# parallella_io.net
KiCad netlist of a schematic drawn in EAGLE
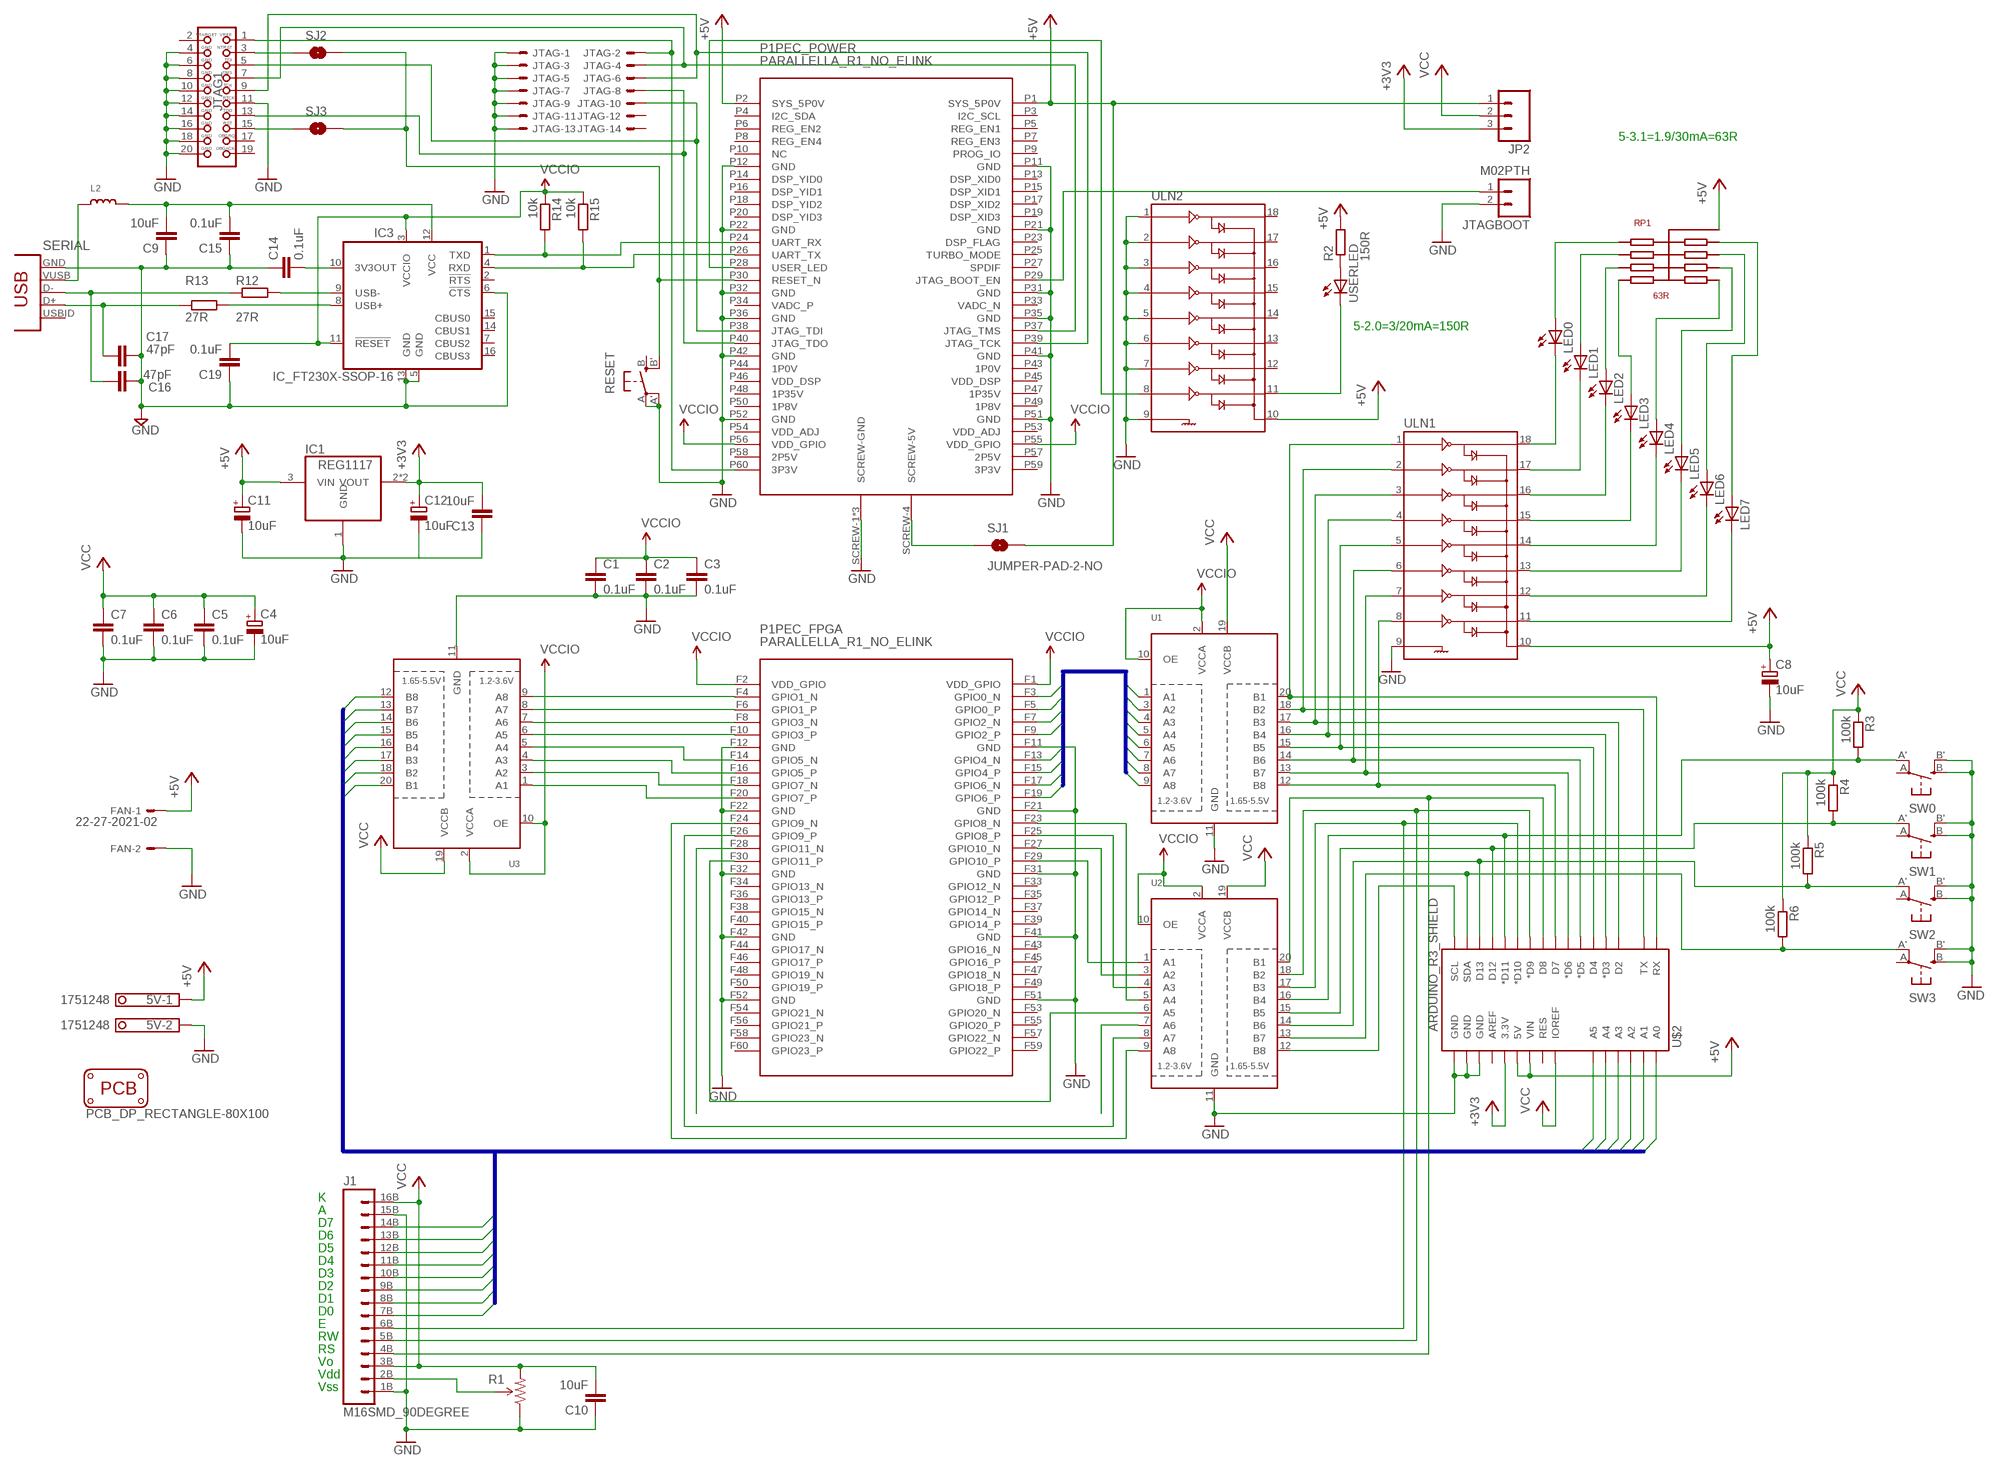
[diagram p0: schematic, sheet 1]

(export (version "E")
  (design (tool "Eeschema 10.0.6"))
  (components
    (comp (ref "5V")
      (value "1751248")
      (footprint "eagle-import:1751248")
      (libsource (lib "eagle-import") (part "1751248"))
    )
    (comp (ref "C1")
      (value "0.1uF")
      (footprint "eagle-import:C0603-N")
      (libsource (lib "eagle-import") (part "C-EUC0603-N"))
    )
    (comp (ref "C2")
      (value "0.1uF")
      (footprint "eagle-import:C0603-N")
      (libsource (lib "eagle-import") (part "C-EUC0603-N"))
    )
    (comp (ref "C3")
      (value "0.1uF")
      (footprint "eagle-import:C0603-N")
      (libsource (lib "eagle-import") (part "C-EUC0603-N"))
    )
    (comp (ref "C4")
      (value "10uF")
      (footprint "eagle-import:D_7343-31W")
      (libsource (lib "eagle-import") (part "CPOL-EUD/7343-31W"))
    )
    (comp (ref "C5")
      (value "0.1uF")
      (footprint "eagle-import:C0603-N")
      (libsource (lib "eagle-import") (part "C-EUC0603-N"))
    )
    (comp (ref "C6")
      (value "0.1uF")
      (footprint "eagle-import:C0603-N")
      (libsource (lib "eagle-import") (part "C-EUC0603-N"))
    )
    (comp (ref "C7")
      (value "0.1uF")
      (footprint "eagle-import:C0603-N")
      (libsource (lib "eagle-import") (part "C-EUC0603-N"))
    )
    (comp (ref "C8")
      (value "10uF")
      (footprint "eagle-import:D_7343-31W")
      (libsource (lib "eagle-import") (part "CPOL-EUD/7343-31W"))
    )
    (comp (ref "C9")
      (value "10uF")
      (footprint "eagle-import:C0603-N")
      (libsource (lib "eagle-import") (part "C-EUC0603-N"))
    )
    (comp (ref "C10")
      (value "10uF")
      (footprint "eagle-import:C0603-N")
      (libsource (lib "eagle-import") (part "C-EUC0603-N"))
    )
    (comp (ref "C11")
      (value "10uF")
      (footprint "eagle-import:D_7343-31W")
      (libsource (lib "eagle-import") (part "CPOL-EUD/7343-31W"))
    )
    (comp (ref "C12")
      (value "10uF")
      (footprint "eagle-import:D_7343-31W")
      (libsource (lib "eagle-import") (part "CPOL-EUD/7343-31W"))
    )
    (comp (ref "C13")
      (value "10uF")
      (footprint "eagle-import:C0603-N")
      (libsource (lib "eagle-import") (part "C-EUC0603-N"))
    )
    (comp (ref "C14")
      (value "0.1uF")
      (footprint "eagle-import:C0603-N")
      (libsource (lib "eagle-import") (part "C-EUC0603-N"))
    )
    (comp (ref "C15")
      (value "0.1uF")
      (footprint "eagle-import:C0603-N")
      (libsource (lib "eagle-import") (part "C-EUC0603-N"))
    )
    (comp (ref "C16")
      (value "47pF")
      (footprint "eagle-import:C0603-N")
      (libsource (lib "eagle-import") (part "C-EUC0603-N"))
    )
    (comp (ref "C17")
      (value "47pF")
      (footprint "eagle-import:C0603-N")
      (libsource (lib "eagle-import") (part "C-EUC0603-N"))
    )
    (comp (ref "C19")
      (value "0.1uF")
      (footprint "eagle-import:C0603-N")
      (libsource (lib "eagle-import") (part "C-EUC0603-N"))
    )
    (comp (ref "FAN")
      (value "22-27-2021-02")
      (footprint "eagle-import:6410-02")
      (libsource (lib "eagle-import") (part "22-?-0227-2021"))
    )
    (comp (ref "IC1")
      (value "REG1117")
      (footprint "eagle-import:SOT223")
      (libsource (lib "eagle-import") (part "REG1117"))
    )
    (comp (ref "IC3")
      (value "IC_FT230X-SSOP-16")
      (footprint "eagle-import:SSOP-16-FTDI")
      (libsource (lib "eagle-import") (part "IC_FT230X-SSOP-16"))
    )
    (comp (ref "J1")
      (value "M16SMD_90DEGREE")
      (footprint "eagle-import:1X16_SMD_90DEGREE")
      (libsource (lib "eagle-import") (part "M16SMD_90DEGREE"))
    )
    (comp (ref "JP2")
      (value "M03LONGPADS")
      (footprint "eagle-import:1X03_LONGPADS")
      (libsource (lib "eagle-import") (part "M03LONGPADS"))
    )
    (comp (ref "JTAG")
      (value "87758-1416")
      (footprint "eagle-import:87758-1416")
      (fields (field (name "MF") "MOLEX") (field (name "MOUSER") "538-87833-5320"))
      (libsource (lib "eagle-import") (part "87758-1416"))
    )
    (comp (ref "JTAG1")
      (value "JTAG-ARM")
      (footprint "eagle-import:JTAG-ARM")
      (libsource (lib "eagle-import") (part "JTAG-ARM"))
    )
    (comp (ref "JTAGBOOT")
      (value "M02PTH")
      (footprint "eagle-import:1X02")
      (libsource (lib "eagle-import") (part "M02PTH"))
    )
    (comp (ref "L2")
      (value "INDUCTOR0805")
      (footprint "eagle-import:0805")
      (libsource (lib "eagle-import") (part "INDUCTOR0805"))
    )
    (comp (ref "LED0")
      (value "LED1206")
      (footprint "eagle-import:LED-1206")
      (libsource (lib "eagle-import") (part "LED1206"))
    )
    (comp (ref "LED1")
      (value "LED1206")
      (footprint "eagle-import:LED-1206")
      (libsource (lib "eagle-import") (part "LED1206"))
    )
    (comp (ref "LED2")
      (value "LED1206")
      (footprint "eagle-import:LED-1206")
      (libsource (lib "eagle-import") (part "LED1206"))
    )
    (comp (ref "LED3")
      (value "LED1206")
      (footprint "eagle-import:LED-1206")
      (libsource (lib "eagle-import") (part "LED1206"))
    )
    (comp (ref "LED4")
      (value "LED1206")
      (footprint "eagle-import:LED-1206")
      (libsource (lib "eagle-import") (part "LED1206"))
    )
    (comp (ref "LED5")
      (value "LED1206")
      (footprint "eagle-import:LED-1206")
      (libsource (lib "eagle-import") (part "LED1206"))
    )
    (comp (ref "LED6")
      (value "LED1206")
      (footprint "eagle-import:LED-1206")
      (libsource (lib "eagle-import") (part "LED1206"))
    )
    (comp (ref "LED7")
      (value "LED1206")
      (footprint "eagle-import:LED-1206")
      (libsource (lib "eagle-import") (part "LED1206"))
    )
    (comp (ref "P1")
      (value "PARALLELLA_R1_NO_ELINK")
      (footprint "eagle-import:PARALLELLA_R1_NO_ELINK")
      (libsource (lib "eagle-import") (part "PARALLELLA_R1_NO_ELINK"))
    )
    (comp (ref "PCB1")
      (value "PCB_DP_RECTANGLE-80X100")
      (footprint "eagle-import:DP10080_V1")
      (libsource (lib "eagle-import") (part "PCB_DP_RECTANGLE-80X100"))
    )
    (comp (ref "R1")
      (value "TRIMPOT")
      (footprint "eagle-import:TRIMPOT-5MM-V2")
      (libsource (lib "eagle-import") (part "TRIMPOT"))
    )
    (comp (ref "R2")
      (value "150R")
      (footprint "eagle-import:R0603-N")
      (libsource (lib "eagle-import") (part "R-EU_R0603-N"))
    )
    (comp (ref "R3")
      (value "100k")
      (footprint "eagle-import:R0603-N")
      (libsource (lib "eagle-import") (part "R-EU_R0603-N"))
    )
    (comp (ref "R4")
      (value "100k")
      (footprint "eagle-import:R0603-N")
      (libsource (lib "eagle-import") (part "R-EU_R0603-N"))
    )
    (comp (ref "R5")
      (value "100k")
      (footprint "eagle-import:R0603-N")
      (libsource (lib "eagle-import") (part "R-EU_R0603-N"))
    )
    (comp (ref "R6")
      (value "100k")
      (footprint "eagle-import:R0603-N")
      (libsource (lib "eagle-import") (part "R-EU_R0603-N"))
    )
    (comp (ref "R12")
      (value "27R")
      (footprint "eagle-import:R0603-N")
      (libsource (lib "eagle-import") (part "R-EU_R0603-N"))
    )
    (comp (ref "R13")
      (value "27R")
      (footprint "eagle-import:R0603-N")
      (libsource (lib "eagle-import") (part "R-EU_R0603-N"))
    )
    (comp (ref "R14")
      (value "10k")
      (footprint "eagle-import:R0603-S")
      (libsource (lib "eagle-import") (part "R-EU_R0603-S"))
    )
    (comp (ref "R15")
      (value "10k")
      (footprint "eagle-import:R0603-N")
      (libsource (lib "eagle-import") (part "R-EU_R0603-N"))
    )
    (comp (ref "RESET")
      (value "SPST_TACT-EVQQ2")
      (footprint "eagle-import:EVQ-Q2")
      (libsource (lib "eagle-import") (part "SPST_TACT-EVQQ2"))
    )
    (comp (ref "RP1")
      (value "63R")
      (footprint "eagle-import:745C10")
      (libsource (lib "eagle-import") (part "745C101745C101"))
    )
    (comp (ref "SERIAL")
      (value "CON-USB-F-MINI-B")
      (footprint "eagle-import:CONN_USB_MINI-B")
      (libsource (lib "eagle-import") (part "CON-USB-F-MINI-B"))
    )
    (comp (ref "SJ1")
      (value "JUMPER-PAD-2-NO")
      (footprint "eagle-import:PAD-JUMPER-2-NO_NO_SILK")
      (libsource (lib "eagle-import") (part "JUMPER-PAD-2-NO"))
    )
    (comp (ref "SJ2")
      (value "JUMPER-PAD-2-NO")
      (footprint "eagle-import:PAD-JUMPER-2-NO_NO_SILK")
      (libsource (lib "eagle-import") (part "JUMPER-PAD-2-NO"))
    )
    (comp (ref "SJ3")
      (value "JUMPER-PAD-2-NO")
      (footprint "eagle-import:PAD-JUMPER-2-NO_NO_SILK")
      (libsource (lib "eagle-import") (part "JUMPER-PAD-2-NO"))
    )
    (comp (ref "SW0")
      (value "SPST_TACT-EVQQ2")
      (footprint "eagle-import:EVQ-Q2")
      (libsource (lib "eagle-import") (part "SPST_TACT-EVQQ2"))
    )
    (comp (ref "SW1")
      (value "SPST_TACT-EVQQ2")
      (footprint "eagle-import:EVQ-Q2")
      (libsource (lib "eagle-import") (part "SPST_TACT-EVQQ2"))
    )
    (comp (ref "SW2")
      (value "SPST_TACT-EVQQ2")
      (footprint "eagle-import:EVQ-Q2")
      (libsource (lib "eagle-import") (part "SPST_TACT-EVQQ2"))
    )
    (comp (ref "SW3")
      (value "SPST_TACT-EVQQ2")
      (footprint "eagle-import:EVQ-Q2")
      (libsource (lib "eagle-import") (part "SPST_TACT-EVQQ2"))
    )
    (comp (ref "U$2")
      (value "ARDUINO_R3_SHIELD")
      (footprint "eagle-import:UNO_R3_SHIELD")
      (libsource (lib "eagle-import") (part "ARDUINO_R3_SHIELD"))
    )
    (comp (ref "U1")
      (value "TXB0108PWR")
      (footprint "eagle-import:TSSOP20")
      (libsource (lib "eagle-import") (part "TXB0108PWR"))
    )
    (comp (ref "U2")
      (value "TXB0108PWR")
      (footprint "eagle-import:TSSOP20")
      (libsource (lib "eagle-import") (part "TXB0108PWR"))
    )
    (comp (ref "U3")
      (value "TXB0108PWR")
      (footprint "eagle-import:TSSOP20")
      (libsource (lib "eagle-import") (part "TXB0108PWR"))
    )
    (comp (ref "ULN1")
      (value "ULN2803SOICW")
      (footprint "eagle-import:SO18L")
      (libsource (lib "eagle-import") (part "ULN2803SOICW"))
    )
    (comp (ref "ULN2")
      (value "ULN2803SOICW")
      (footprint "eagle-import:SO18L")
      (libsource (lib "eagle-import") (part "ULN2803SOICW"))
    )
    (comp (ref "USERLED")
      (value "LED1206")
      (footprint "eagle-import:LED-1206")
      (libsource (lib "eagle-import") (part "LED1206"))
    )
  )
  (nets
    (net (code "1") (name "+3V3") (class "Default")
      (node (ref "C12") (pin "+") (pinfunction "+_+") (pintype "passive"))
      (node (ref "C13") (pin "2") (pinfunction "2_2") (pintype "passive"))
      (node (ref "IC1") (pin "2") (pinfunction "VOUT_2") (pintype "power_in"))
      (node (ref "IC1") (pin "4") (pinfunction "VOUT_4") (pintype "power_in"))
      (node (ref "JP2") (pin "3") (pinfunction "3_3") (pintype "passive"))
      (node (ref "U$2") (pin "3.3V") (pinfunction "3.3V_3.3V") (pintype "bidirectional"))
    )
    (net (code "2") (name "+5V") (class "Default")
      (node (ref "5V") (pin "1") (pinfunction "K_1") (pintype "passive"))
      (node (ref "C11") (pin "+") (pinfunction "+_+") (pintype "passive"))
      (node (ref "C8") (pin "+") (pinfunction "+_+") (pintype "passive"))
      (node (ref "FAN") (pin "1") (pinfunction "S_1") (pintype "passive"))
      (node (ref "IC1") (pin "3") (pinfunction "VIN_3") (pintype "input"))
      (node (ref "JP2") (pin "1") (pinfunction "1_1") (pintype "passive"))
      (node (ref "P1") (pin "P1") (pinfunction "SYS_5P0V_P1") (pintype "passive"))
      (node (ref "P1") (pin "P2") (pinfunction "SYS_5P0V_P2") (pintype "passive"))
      (node (ref "R2") (pin "2") (pinfunction "2_2") (pintype "passive"))
      (node (ref "RP1") (pin "1") (pinfunction "COMMON_1") (pintype "bidirectional"))
      (node (ref "RP1") (pin "6") (pinfunction "COMMON_6") (pintype "bidirectional"))
      (node (ref "SJ1") (pin "2") (pinfunction "2_2") (pintype "passive"))
      (node (ref "U$2") (pin "5V") (pinfunction "5V_5V") (pintype "bidirectional"))
      (node (ref "U$2") (pin "VIN") (pinfunction "VIN_VIN") (pintype "bidirectional"))
      (node (ref "ULN1") (pin "10") (pinfunction "10_10") (pintype "bidirectional"))
      (node (ref "ULN2") (pin "10") (pinfunction "10_10") (pintype "bidirectional"))
    )
    (net (code "3") (name "/A0") (class "Default")
      (node (ref "J1") (pin "7B") (pinfunction "7_7B") (pintype "passive"))
      (node (ref "U$2") (pin "A0") (pinfunction "A0_A0") (pintype "bidirectional"))
      (node (ref "U3") (pin "20") (pinfunction "B1_20") (pintype "bidirectional"))
    )
    (net (code "4") (name "/A1") (class "Default")
      (node (ref "J1") (pin "8B") (pinfunction "8_8B") (pintype "passive"))
      (node (ref "U$2") (pin "A1") (pinfunction "A1_A1") (pintype "bidirectional"))
      (node (ref "U3") (pin "18") (pinfunction "B2_18") (pintype "bidirectional"))
    )
    (net (code "5") (name "/A2") (class "Default")
      (node (ref "J1") (pin "9B") (pinfunction "9_9B") (pintype "passive"))
      (node (ref "U$2") (pin "A2") (pinfunction "A2_A2") (pintype "bidirectional"))
      (node (ref "U3") (pin "17") (pinfunction "B3_17") (pintype "bidirectional"))
    )
    (net (code "6") (name "/A3") (class "Default")
      (node (ref "J1") (pin "10B") (pinfunction "10_10B") (pintype "passive"))
      (node (ref "U$2") (pin "A3") (pinfunction "A3_A3") (pintype "bidirectional"))
      (node (ref "U3") (pin "16") (pinfunction "B4_16") (pintype "bidirectional"))
    )
    (net (code "7") (name "/A4") (class "Default")
      (node (ref "J1") (pin "11B") (pinfunction "11_11B") (pintype "passive"))
      (node (ref "U$2") (pin "A4") (pinfunction "A4_A4") (pintype "bidirectional"))
      (node (ref "U3") (pin "15") (pinfunction "B5_15") (pintype "bidirectional"))
    )
    (net (code "8") (name "/A5") (class "Default")
      (node (ref "J1") (pin "12B") (pinfunction "12_12B") (pintype "passive"))
      (node (ref "U$2") (pin "A5") (pinfunction "A5_A5") (pintype "bidirectional"))
      (node (ref "U3") (pin "14") (pinfunction "B6_14") (pintype "bidirectional"))
    )
    (net (code "9") (name "/A6") (class "Default")
      (node (ref "J1") (pin "13B") (pinfunction "13_13B") (pintype "passive"))
      (node (ref "U3") (pin "13") (pinfunction "B7_13") (pintype "bidirectional"))
    )
    (net (code "10") (name "/A7") (class "Default")
      (node (ref "J1") (pin "14B") (pinfunction "14_14B") (pintype "passive"))
      (node (ref "U3") (pin "12") (pinfunction "B8_12") (pintype "bidirectional"))
    )
    (net (code "11") (name "/B0") (class "Default")
      (node (ref "P1") (pin "F19") (pinfunction "GPIO6_P_F19") (pintype "bidirectional"))
      (node (ref "U1") (pin "1") (pinfunction "A1_1") (pintype "bidirectional"))
    )
    (net (code "12") (name "/B1") (class "Default")
      (node (ref "P1") (pin "F17") (pinfunction "GPIO6_N_F17") (pintype "bidirectional"))
      (node (ref "U1") (pin "3") (pinfunction "A2_3") (pintype "bidirectional"))
    )
    (net (code "13") (name "/B2") (class "Default")
      (node (ref "P1") (pin "F15") (pinfunction "GPIO4_P_F15") (pintype "bidirectional"))
      (node (ref "U1") (pin "4") (pinfunction "A3_4") (pintype "bidirectional"))
    )
    (net (code "14") (name "/B3") (class "Default")
      (node (ref "P1") (pin "F13") (pinfunction "GPIO4_N_F13") (pintype "bidirectional"))
      (node (ref "U1") (pin "5") (pinfunction "A4_5") (pintype "bidirectional"))
    )
    (net (code "15") (name "/B4") (class "Default")
      (node (ref "P1") (pin "F9") (pinfunction "GPIO2_P_F9") (pintype "bidirectional"))
      (node (ref "U1") (pin "6") (pinfunction "A5_6") (pintype "bidirectional"))
    )
    (net (code "16") (name "/B5") (class "Default")
      (node (ref "P1") (pin "F7") (pinfunction "GPIO2_N_F7") (pintype "bidirectional"))
      (node (ref "U1") (pin "7") (pinfunction "A6_7") (pintype "bidirectional"))
    )
    (net (code "17") (name "/B6") (class "Default")
      (node (ref "P1") (pin "F5") (pinfunction "GPIO0_P_F5") (pintype "bidirectional"))
      (node (ref "U1") (pin "8") (pinfunction "A7_8") (pintype "bidirectional"))
    )
    (net (code "18") (name "/B7") (class "Default")
      (node (ref "P1") (pin "F3") (pinfunction "GPIO0_N_F3") (pintype "bidirectional"))
      (node (ref "U1") (pin "9") (pinfunction "A8_9") (pintype "bidirectional"))
    )
    (net (code "19") (name "GND") (class "Default")
      (node (ref "5V") (pin "2") (pinfunction "K_2") (pintype "passive"))
      (node (ref "C1") (pin "2") (pinfunction "2_2") (pintype "passive"))
      (node (ref "C10") (pin "1") (pinfunction "1_1") (pintype "passive"))
      (node (ref "C11") (pin "-") (pinfunction "-_-") (pintype "passive"))
      (node (ref "C12") (pin "-") (pinfunction "-_-") (pintype "passive"))
      (node (ref "C13") (pin "1") (pinfunction "1_1") (pintype "passive"))
      (node (ref "C14") (pin "1") (pinfunction "1_1") (pintype "passive"))
      (node (ref "C15") (pin "1") (pinfunction "1_1") (pintype "passive"))
      (node (ref "C16") (pin "2") (pinfunction "2_2") (pintype "passive"))
      (node (ref "C17") (pin "2") (pinfunction "2_2") (pintype "passive"))
      (node (ref "C19") (pin "1") (pinfunction "1_1") (pintype "passive"))
      (node (ref "C2") (pin "2") (pinfunction "2_2") (pintype "passive"))
      (node (ref "C3") (pin "2") (pinfunction "2_2") (pintype "passive"))
      (node (ref "C4") (pin "-") (pinfunction "-_-") (pintype "passive"))
      (node (ref "C5") (pin "2") (pinfunction "2_2") (pintype "passive"))
      (node (ref "C6") (pin "2") (pinfunction "2_2") (pintype "passive"))
      (node (ref "C7") (pin "2") (pinfunction "2_2") (pintype "passive"))
      (node (ref "C8") (pin "-") (pinfunction "-_-") (pintype "passive"))
      (node (ref "C9") (pin "1") (pinfunction "1_1") (pintype "passive"))
      (node (ref "FAN") (pin "2") (pinfunction "S_2") (pintype "passive"))
      (node (ref "IC1") (pin "1") (pinfunction "GND_1") (pintype "power_in"))
      (node (ref "IC3") (pin "13") (pinfunction "GND_13") (pintype "power_in"))
      (node (ref "IC3") (pin "5") (pinfunction "GND_5") (pintype "power_in"))
      (node (ref "IC3") (pin "6") (pinfunction "~{CTS}_6") (pintype "bidirectional"))
      (node (ref "J1") (pin "15B") (pinfunction "15_15B") (pintype "passive"))
      (node (ref "J1") (pin "1B") (pinfunction "1_1B") (pintype "passive"))
      (node (ref "JTAG") (pin "1") (pinfunction "S_1") (pintype "passive"))
      (node (ref "JTAG") (pin "11") (pinfunction "S_11") (pintype "passive"))
      (node (ref "JTAG") (pin "13") (pinfunction "S_13") (pintype "passive"))
      (node (ref "JTAG") (pin "3") (pinfunction "S_3") (pintype "passive"))
      (node (ref "JTAG") (pin "5") (pinfunction "S_5") (pintype "passive"))
      (node (ref "JTAG") (pin "7") (pinfunction "S_7") (pintype "passive"))
      (node (ref "JTAG") (pin "9") (pinfunction "S_9") (pintype "passive"))
      (node (ref "JTAG1") (pin "10") (pinfunction "10_10") (pintype "passive"))
      (node (ref "JTAG1") (pin "11") (pinfunction "11_11") (pintype "passive"))
      (node (ref "JTAG1") (pin "12") (pinfunction "12_12") (pintype "passive"))
      (node (ref "JTAG1") (pin "14") (pinfunction "14_14") (pintype "passive"))
      (node (ref "JTAG1") (pin "16") (pinfunction "16_16") (pintype "passive"))
      (node (ref "JTAG1") (pin "18") (pinfunction "18_18") (pintype "passive"))
      (node (ref "JTAG1") (pin "20") (pinfunction "20_20") (pintype "passive"))
      (node (ref "JTAG1") (pin "4") (pinfunction "4_4") (pintype "passive"))
      (node (ref "JTAG1") (pin "6") (pinfunction "6_6") (pintype "passive"))
      (node (ref "JTAG1") (pin "8") (pinfunction "8_8") (pintype "passive"))
      (node (ref "JTAGBOOT") (pin "2") (pinfunction "2_2") (pintype "passive"))
      (node (ref "P1") (pin "F11") (pinfunction "GND_F11") (pintype "passive"))
      (node (ref "P1") (pin "F12") (pinfunction "GND_F12") (pintype "passive"))
      (node (ref "P1") (pin "F21") (pinfunction "GND_F21") (pintype "passive"))
      (node (ref "P1") (pin "F22") (pinfunction "GND_F22") (pintype "passive"))
      (node (ref "P1") (pin "F31") (pinfunction "GND_F31") (pintype "passive"))
      (node (ref "P1") (pin "F32") (pinfunction "GND_F32") (pintype "passive"))
      (node (ref "P1") (pin "F41") (pinfunction "GND_F41") (pintype "passive"))
      (node (ref "P1") (pin "F42") (pinfunction "GND_F42") (pintype "passive"))
      (node (ref "P1") (pin "F51") (pinfunction "GND_F51") (pintype "passive"))
      (node (ref "P1") (pin "F52") (pinfunction "GND_F52") (pintype "passive"))
      (node (ref "P1") (pin "P11") (pinfunction "GND_P11") (pintype "passive"))
      (node (ref "P1") (pin "P12") (pinfunction "GND_P12") (pintype "passive"))
      (node (ref "P1") (pin "P21") (pinfunction "GND_P21") (pintype "passive"))
      (node (ref "P1") (pin "P22") (pinfunction "GND_P22") (pintype "passive"))
      (node (ref "P1") (pin "P31") (pinfunction "GND_P31") (pintype "passive"))
      (node (ref "P1") (pin "P32") (pinfunction "GND_P32") (pintype "passive"))
      (node (ref "P1") (pin "P35") (pinfunction "GND_P35") (pintype "passive"))
      (node (ref "P1") (pin "P36") (pinfunction "GND_P36") (pintype "passive"))
      (node (ref "P1") (pin "P41") (pinfunction "GND_P41") (pintype "passive"))
      (node (ref "P1") (pin "P42") (pinfunction "GND_P42") (pintype "passive"))
      (node (ref "P1") (pin "P51") (pinfunction "GND_P51") (pintype "passive"))
      (node (ref "P1") (pin "P52") (pinfunction "GND_P52") (pintype "passive"))
      (node (ref "P1") (pin "SCREW-1") (pinfunction "SCREW-GND_SCREW-1") (pintype "power_in"))
      (node (ref "P1") (pin "SCREW-2") (pinfunction "SCREW-GND_SCREW-2") (pintype "power_in"))
      (node (ref "P1") (pin "SCREW-3") (pinfunction "SCREW-GND_SCREW-3") (pintype "power_in"))
      (node (ref "R1") (pin "A") (pinfunction "CCW_A") (pintype "passive"))
      (node (ref "RESET") (pin "A") (pinfunction "P_A") (pintype "passive"))
      (node (ref "RESET") (pin "A'") (pinfunction "P1_A'") (pintype "passive"))
      (node (ref "SERIAL") (pin "GND") (pinfunction "GND_GND") (pintype "bidirectional"))
      (node (ref "SW0") (pin "B") (pinfunction "S_B") (pintype "passive"))
      (node (ref "SW0") (pin "B'") (pinfunction "S1_B'") (pintype "passive"))
      (node (ref "SW1") (pin "B") (pinfunction "S_B") (pintype "passive"))
      (node (ref "SW1") (pin "B'") (pinfunction "S1_B'") (pintype "passive"))
      (node (ref "SW2") (pin "B") (pinfunction "S_B") (pintype "passive"))
      (node (ref "SW2") (pin "B'") (pinfunction "S1_B'") (pintype "passive"))
      (node (ref "SW3") (pin "B") (pinfunction "S_B") (pintype "passive"))
      (node (ref "SW3") (pin "B'") (pinfunction "S1_B'") (pintype "passive"))
      (node (ref "U$2") (pin "GND@0") (pinfunction "GND_GND@0") (pintype "bidirectional"))
      (node (ref "U$2") (pin "GND@1") (pinfunction "GND_GND@1") (pintype "bidirectional"))
      (node (ref "U$2") (pin "GND@2") (pinfunction "GND_GND@2") (pintype "bidirectional"))
      (node (ref "U1") (pin "11") (pinfunction "GND_11") (pintype "bidirectional"))
      (node (ref "U2") (pin "11") (pinfunction "GND_11") (pintype "bidirectional"))
      (node (ref "U3") (pin "11") (pinfunction "GND_11") (pintype "bidirectional"))
      (node (ref "ULN1") (pin "9") (pinfunction "9_9") (pintype "bidirectional"))
      (node (ref "ULN2") (pin "1") (pinfunction "1_1") (pintype "bidirectional"))
      (node (ref "ULN2") (pin "2") (pinfunction "2_2") (pintype "bidirectional"))
      (node (ref "ULN2") (pin "3") (pinfunction "3_3") (pintype "bidirectional"))
      (node (ref "ULN2") (pin "4") (pinfunction "4_4") (pintype "bidirectional"))
      (node (ref "ULN2") (pin "5") (pinfunction "5_5") (pintype "bidirectional"))
      (node (ref "ULN2") (pin "6") (pinfunction "6_6") (pintype "bidirectional"))
      (node (ref "ULN2") (pin "7") (pinfunction "7_7") (pintype "bidirectional"))
      (node (ref "ULN2") (pin "9") (pinfunction "9_9") (pintype "bidirectional"))
    )
    (net (code "20") (name "Net-(C16-Pad1)") (class "Default")
      (node (ref "C16") (pin "1") (pinfunction "1_1") (pintype "passive"))
      (node (ref "R12") (pin "1") (pinfunction "1_1") (pintype "passive"))
      (node (ref "SERIAL") (pin "D-") (pinfunction "D-_D-") (pintype "bidirectional"))
    )
    (net (code "21") (name "Net-(C17-Pad1)") (class "Default")
      (node (ref "C17") (pin "1") (pinfunction "1_1") (pintype "passive"))
      (node (ref "R13") (pin "1") (pinfunction "1_1") (pintype "passive"))
      (node (ref "SERIAL") (pin "D+") (pinfunction "D+_D+") (pintype "bidirectional"))
    )
    (net (code "22") (name "Net-(IC3-3V3OUT)") (class "Default")
      (node (ref "C14") (pin "2") (pinfunction "2_2") (pintype "passive"))
      (node (ref "IC3") (pin "10") (pinfunction "3V3OUT_10") (pintype "power_in"))
    )
    (net (code "23") (name "Net-(IC3-RXD)") (class "Default")
      (node (ref "IC3") (pin "4") (pinfunction "RXD_4") (pintype "input"))
      (node (ref "P1") (pin "P26") (pinfunction "UART_TX_P26") (pintype "output"))
      (node (ref "R15") (pin "2") (pinfunction "2_2") (pintype "passive"))
    )
    (net (code "24") (name "Net-(IC3-TXD)") (class "Default")
      (node (ref "IC3") (pin "1") (pinfunction "TXD_1") (pintype "output"))
      (node (ref "P1") (pin "P24") (pinfunction "UART_RX_P24") (pintype "input"))
      (node (ref "R14") (pin "2") (pinfunction "2_2") (pintype "passive"))
    )
    (net (code "25") (name "Net-(IC3-USB+)") (class "Default")
      (node (ref "IC3") (pin "8") (pinfunction "USB+_8") (pintype "output"))
      (node (ref "R13") (pin "2") (pinfunction "2_2") (pintype "passive"))
    )
    (net (code "26") (name "Net-(IC3-USB-)") (class "Default")
      (node (ref "IC3") (pin "9") (pinfunction "USB-_9") (pintype "input"))
      (node (ref "R12") (pin "2") (pinfunction "2_2") (pintype "passive"))
    )
    (net (code "27") (name "Net-(IC3-VCC)") (class "Default")
      (node (ref "C15") (pin "2") (pinfunction "2_2") (pintype "passive"))
      (node (ref "C9") (pin "2") (pinfunction "2_2") (pintype "passive"))
      (node (ref "IC3") (pin "12") (pinfunction "VCC_12") (pintype "power_in"))
      (node (ref "L2") (pin "2") (pinfunction "2_2") (pintype "passive"))
    )
    (net (code "28") (name "Net-(J1-2)") (class "Default")
      (node (ref "J1") (pin "2B") (pinfunction "2_2B") (pintype "passive"))
      (node (ref "R1") (pin "B") (pinfunction "WIPER_B") (pintype "passive"))
    )
    (net (code "29") (name "Net-(J1-4)") (class "Default")
      (node (ref "J1") (pin "4B") (pinfunction "4_4B") (pintype "passive"))
      (node (ref "U$2") (pin "D8") (pinfunction "D8_D8") (pintype "bidirectional"))
      (node (ref "U2") (pin "20") (pinfunction "B1_20") (pintype "bidirectional"))
    )
    (net (code "30") (name "Net-(J1-5)") (class "Default")
      (node (ref "J1") (pin "5B") (pinfunction "5_5B") (pintype "passive"))
      (node (ref "U$2") (pin "D9") (pinfunction "*D9_D9") (pintype "bidirectional"))
      (node (ref "U2") (pin "18") (pinfunction "B2_18") (pintype "bidirectional"))
    )
    (net (code "31") (name "Net-(J1-6)") (class "Default")
      (node (ref "J1") (pin "6B") (pinfunction "6_6B") (pintype "passive"))
      (node (ref "U$2") (pin "D10") (pinfunction "*D10_D10") (pintype "bidirectional"))
      (node (ref "U2") (pin "17") (pinfunction "B3_17") (pintype "bidirectional"))
    )
    (net (code "32") (name "Net-(JTAG1-Pad3)") (class "Default")
      (node (ref "JTAG1") (pin "3") (pinfunction "3_3") (pintype "passive"))
      (node (ref "SJ2") (pin "1") (pinfunction "1_1") (pintype "passive"))
    )
    (net (code "33") (name "Net-(JTAG1-Pad15)") (class "Default")
      (node (ref "JTAG1") (pin "15") (pinfunction "15_15") (pintype "passive"))
      (node (ref "SJ3") (pin "1") (pinfunction "1_1") (pintype "passive"))
    )
    (net (code "34") (name "Net-(JTAGB-S)") (class "Default")
      (node (ref "JTAG") (pin "10") (pinfunction "S_10") (pintype "passive"))
      (node (ref "JTAG1") (pin "5") (pinfunction "5_5") (pintype "passive"))
      (node (ref "P1") (pin "P38") (pinfunction "JTAG_TDI_P38") (pintype "input"))
    )
    (net (code "35") (name "Net-(JTAGG-S)") (class "Default")
      (node (ref "JTAG") (pin "2") (pinfunction "S_2") (pintype "passive"))
      (node (ref "JTAG1") (pin "1") (pinfunction "1_1") (pintype "passive"))
      (node (ref "P1") (pin "P60") (pinfunction "3P3V_P60") (pintype "passive"))
    )
    (net (code "36") (name "Net-(JTAGI-S)") (class "Default")
      (node (ref "JTAG") (pin "4") (pinfunction "S_4") (pintype "passive"))
      (node (ref "JTAG1") (pin "7") (pinfunction "7_7") (pintype "passive"))
      (node (ref "P1") (pin "P37") (pinfunction "JTAG_TMS_P37") (pintype "input"))
    )
    (net (code "37") (name "Net-(JTAGK-S)") (class "Default")
      (node (ref "JTAG") (pin "6") (pinfunction "S_6") (pintype "passive"))
      (node (ref "JTAG1") (pin "9") (pinfunction "9_9") (pintype "passive"))
      (node (ref "P1") (pin "P39") (pinfunction "JTAG_TCK_P39") (pintype "input"))
    )
    (net (code "38") (name "Net-(JTAGM-S)") (class "Default")
      (node (ref "JTAG") (pin "8") (pinfunction "S_8") (pintype "passive"))
      (node (ref "JTAG1") (pin "13") (pinfunction "13_13") (pintype "passive"))
      (node (ref "P1") (pin "P40") (pinfunction "JTAG_TDO_P40") (pintype "output"))
    )
    (net (code "39") (name "Net-(L2-Pad1)") (class "Default")
      (node (ref "L2") (pin "1") (pinfunction "1_1") (pintype "passive"))
      (node (ref "SERIAL") (pin "VUSB") (pinfunction "VUSB_VUSB") (pintype "bidirectional"))
    )
    (net (code "40") (name "Net-(LED0-PadC)") (class "Default")
      (node (ref "LED0") (pin "C") (pinfunction "C_C") (pintype "passive"))
      (node (ref "ULN1") (pin "18") (pinfunction "18_18") (pintype "bidirectional"))
    )
    (net (code "41") (name "Net-(LED1-PadC)") (class "Default")
      (node (ref "LED1") (pin "C") (pinfunction "C_C") (pintype "passive"))
      (node (ref "ULN1") (pin "17") (pinfunction "17_17") (pintype "bidirectional"))
    )
    (net (code "42") (name "Net-(LED2-PadC)") (class "Default")
      (node (ref "LED2") (pin "C") (pinfunction "C_C") (pintype "passive"))
      (node (ref "ULN1") (pin "16") (pinfunction "16_16") (pintype "bidirectional"))
    )
    (net (code "43") (name "Net-(LED3-PadC)") (class "Default")
      (node (ref "LED3") (pin "C") (pinfunction "C_C") (pintype "passive"))
      (node (ref "ULN1") (pin "15") (pinfunction "15_15") (pintype "bidirectional"))
    )
    (net (code "44") (name "Net-(LED4-PadC)") (class "Default")
      (node (ref "LED4") (pin "C") (pinfunction "C_C") (pintype "passive"))
      (node (ref "ULN1") (pin "14") (pinfunction "14_14") (pintype "bidirectional"))
    )
    (net (code "45") (name "Net-(LED5-PadC)") (class "Default")
      (node (ref "LED5") (pin "C") (pinfunction "C_C") (pintype "passive"))
      (node (ref "ULN1") (pin "13") (pinfunction "13_13") (pintype "bidirectional"))
    )
    (net (code "46") (name "Net-(LED6-PadC)") (class "Default")
      (node (ref "LED6") (pin "C") (pinfunction "C_C") (pintype "passive"))
      (node (ref "ULN1") (pin "12") (pinfunction "12_12") (pintype "bidirectional"))
    )
    (net (code "47") (name "Net-(LED7-PadC)") (class "Default")
      (node (ref "LED7") (pin "C") (pinfunction "C_C") (pintype "passive"))
      (node (ref "ULN1") (pin "11") (pinfunction "11_11") (pintype "bidirectional"))
    )
    (net (code "48") (name "Net-(P1A-GPIO1_N)") (class "Default")
      (node (ref "P1") (pin "F4") (pinfunction "GPIO1_N_F4") (pintype "bidirectional"))
      (node (ref "U3") (pin "9") (pinfunction "A8_9") (pintype "bidirectional"))
    )
    (net (code "49") (name "Net-(P1A-GPIO1_P)") (class "Default")
      (node (ref "P1") (pin "F6") (pinfunction "GPIO1_P_F6") (pintype "bidirectional"))
      (node (ref "U3") (pin "8") (pinfunction "A7_8") (pintype "bidirectional"))
    )
    (net (code "50") (name "Net-(P1A-GPIO3_N)") (class "Default")
      (node (ref "P1") (pin "F8") (pinfunction "GPIO3_N_F8") (pintype "bidirectional"))
      (node (ref "U3") (pin "7") (pinfunction "A6_7") (pintype "bidirectional"))
    )
    (net (code "51") (name "Net-(P1A-GPIO3_P)") (class "Default")
      (node (ref "P1") (pin "F10") (pinfunction "GPIO3_P_F10") (pintype "bidirectional"))
      (node (ref "U3") (pin "6") (pinfunction "A5_6") (pintype "bidirectional"))
    )
    (net (code "52") (name "Net-(P1A-GPIO5_N)") (class "Default")
      (node (ref "P1") (pin "F14") (pinfunction "GPIO5_N_F14") (pintype "bidirectional"))
      (node (ref "U3") (pin "5") (pinfunction "A4_5") (pintype "bidirectional"))
    )
    (net (code "53") (name "Net-(P1A-GPIO5_P)") (class "Default")
      (node (ref "P1") (pin "F16") (pinfunction "GPIO5_P_F16") (pintype "bidirectional"))
      (node (ref "U3") (pin "4") (pinfunction "A3_4") (pintype "bidirectional"))
    )
    (net (code "54") (name "Net-(P1A-GPIO7_N)") (class "Default")
      (node (ref "P1") (pin "F18") (pinfunction "GPIO7_N_F18") (pintype "bidirectional"))
      (node (ref "U3") (pin "3") (pinfunction "A2_3") (pintype "bidirectional"))
    )
    (net (code "55") (name "Net-(P1A-GPIO7_P)") (class "Default")
      (node (ref "P1") (pin "F20") (pinfunction "GPIO7_P_F20") (pintype "bidirectional"))
      (node (ref "U3") (pin "1") (pinfunction "A1_1") (pintype "bidirectional"))
    )
    (net (code "56") (name "Net-(P1A-GPIO8_N)") (class "Default")
      (node (ref "P1") (pin "F23") (pinfunction "GPIO8_N_F23") (pintype "bidirectional"))
      (node (ref "U2") (pin "5") (pinfunction "A4_5") (pintype "bidirectional"))
    )
    (net (code "57") (name "Net-(P1A-GPIO8_P)") (class "Default")
      (node (ref "P1") (pin "F25") (pinfunction "GPIO8_P_F25") (pintype "bidirectional"))
      (node (ref "U2") (pin "4") (pinfunction "A3_4") (pintype "bidirectional"))
    )
    (net (code "58") (name "Net-(P1A-GPIO9_N)") (class "Default")
      (node (ref "P1") (pin "F24") (pinfunction "GPIO9_N_F24") (pintype "bidirectional"))
      (node (ref "U2") (pin "9") (pinfunction "A8_9") (pintype "bidirectional"))
    )
    (net (code "59") (name "Net-(P1A-GPIO9_P)") (class "Default")
      (node (ref "P1") (pin "F26") (pinfunction "GPIO9_P_F26") (pintype "bidirectional"))
      (node (ref "U2") (pin "8") (pinfunction "A7_8") (pintype "bidirectional"))
    )
    (net (code "60") (name "Net-(P1A-GPIO10_N)") (class "Default")
      (node (ref "P1") (pin "F27") (pinfunction "GPIO10_N_F27") (pintype "bidirectional"))
      (node (ref "U2") (pin "3") (pinfunction "A2_3") (pintype "bidirectional"))
    )
    (net (code "61") (name "Net-(P1A-GPIO10_P)") (class "Default")
      (node (ref "P1") (pin "F29") (pinfunction "GPIO10_P_F29") (pintype "bidirectional"))
      (node (ref "U2") (pin "1") (pinfunction "A1_1") (pintype "bidirectional"))
    )
    (net (code "62") (name "Net-(P1A-GPIO11_P)") (class "Default")
      (node (ref "P1") (pin "F30") (pinfunction "GPIO11_P_F30") (pintype "bidirectional"))
      (node (ref "U2") (pin "6") (pinfunction "A5_6") (pintype "bidirectional"))
    )
    (net (code "63") (name "Net-(P1B-JTAG_BOOT_EN)") (class "Default")
      (node (ref "JTAGBOOT") (pin "1") (pinfunction "1_1") (pintype "passive"))
      (node (ref "P1") (pin "P29") (pinfunction "JTAG_BOOT_EN_P29") (pintype "input"))
    )
    (net (code "64") (name "Net-(P1B-RESET_N)") (class "Default")
      (node (ref "P1") (pin "P30") (pinfunction "RESET_N_P30") (pintype "output"))
      (node (ref "RESET") (pin "B'") (pinfunction "S1_B'") (pintype "passive"))
      (node (ref "SJ2") (pin "2") (pinfunction "2_2") (pintype "passive"))
      (node (ref "SJ3") (pin "2") (pinfunction "2_2") (pintype "passive"))
    )
    (net (code "65") (name "Net-(P1B-SCREW-5V)") (class "Default")
      (node (ref "P1") (pin "SCREW-4") (pinfunction "SCREW-5V_SCREW-4") (pintype "power_in"))
      (node (ref "SJ1") (pin "1") (pinfunction "1_1") (pintype "passive"))
    )
    (net (code "66") (name "Net-(P1B-USER_LED)") (class "Default")
      (node (ref "P1") (pin "P28") (pinfunction "USER_LED_P28") (pintype "output"))
      (node (ref "ULN2") (pin "8") (pinfunction "8_8") (pintype "bidirectional"))
    )
    (net (code "67") (name "Net-(R2-Pad1)") (class "Default")
      (node (ref "R2") (pin "1") (pinfunction "1_1") (pintype "passive"))
      (node (ref "USERLED") (pin "A") (pinfunction "A_A") (pintype "passive"))
    )
    (net (code "68") (name "Net-(RP1-R1)") (class "Default")
      (node (ref "LED7") (pin "A") (pinfunction "A_A") (pintype "passive"))
      (node (ref "RP1") (pin "2") (pinfunction "R1_2") (pintype "bidirectional"))
    )
    (net (code "69") (name "Net-(RP1-R2)") (class "Default")
      (node (ref "LED6") (pin "A") (pinfunction "A_A") (pintype "passive"))
      (node (ref "RP1") (pin "3") (pinfunction "R2_3") (pintype "bidirectional"))
    )
    (net (code "70") (name "Net-(RP1-R3)") (class "Default")
      (node (ref "LED5") (pin "A") (pinfunction "A_A") (pintype "passive"))
      (node (ref "RP1") (pin "4") (pinfunction "R3_4") (pintype "bidirectional"))
    )
    (net (code "71") (name "Net-(RP1-R4)") (class "Default")
      (node (ref "LED4") (pin "A") (pinfunction "A_A") (pintype "passive"))
      (node (ref "RP1") (pin "5") (pinfunction "R4_5") (pintype "bidirectional"))
    )
    (net (code "72") (name "Net-(RP1-R5)") (class "Default")
      (node (ref "LED3") (pin "A") (pinfunction "A_A") (pintype "passive"))
      (node (ref "RP1") (pin "7") (pinfunction "R5_7") (pintype "bidirectional"))
    )
    (net (code "73") (name "Net-(RP1-R6)") (class "Default")
      (node (ref "LED2") (pin "A") (pinfunction "A_A") (pintype "passive"))
      (node (ref "RP1") (pin "8") (pinfunction "R6_8") (pintype "bidirectional"))
    )
    (net (code "74") (name "Net-(RP1-R7)") (class "Default")
      (node (ref "LED1") (pin "A") (pinfunction "A_A") (pintype "passive"))
      (node (ref "RP1") (pin "9") (pinfunction "R7_9") (pintype "bidirectional"))
    )
    (net (code "75") (name "Net-(RP1-R8)") (class "Default")
      (node (ref "LED0") (pin "A") (pinfunction "A_A") (pintype "passive"))
      (node (ref "RP1") (pin "10") (pinfunction "R8_10") (pintype "bidirectional"))
    )
    (net (code "76") (name "Net-(SW0-P1)") (class "Default")
      (node (ref "R3") (pin "2") (pinfunction "2_2") (pintype "passive"))
      (node (ref "SW0") (pin "A'") (pinfunction "P1_A'") (pintype "passive"))
      (node (ref "U$2") (pin "D11") (pinfunction "*D11_D11") (pintype "bidirectional"))
      (node (ref "U2") (pin "16") (pinfunction "B4_16") (pintype "bidirectional"))
    )
    (net (code "77") (name "Net-(SW1-P1)") (class "Default")
      (node (ref "R4") (pin "2") (pinfunction "2_2") (pintype "passive"))
      (node (ref "SW1") (pin "A'") (pinfunction "P1_A'") (pintype "passive"))
      (node (ref "U$2") (pin "D12") (pinfunction "D12_D12") (pintype "bidirectional"))
      (node (ref "U2") (pin "15") (pinfunction "B5_15") (pintype "bidirectional"))
    )
    (net (code "78") (name "Net-(SW2-P1)") (class "Default")
      (node (ref "R5") (pin "2") (pinfunction "2_2") (pintype "passive"))
      (node (ref "SW2") (pin "A'") (pinfunction "P1_A'") (pintype "passive"))
      (node (ref "U$2") (pin "D13") (pinfunction "D13_D13") (pintype "bidirectional"))
      (node (ref "U2") (pin "14") (pinfunction "B6_14") (pintype "bidirectional"))
    )
    (net (code "79") (name "Net-(SW3-P1)") (class "Default")
      (node (ref "R6") (pin "2") (pinfunction "2_2") (pintype "passive"))
      (node (ref "SW3") (pin "A'") (pinfunction "P1_A'") (pintype "passive"))
      (node (ref "U$2") (pin "SDA") (pinfunction "SDA_SDA") (pintype "bidirectional"))
      (node (ref "U2") (pin "13") (pinfunction "B7_13") (pintype "bidirectional"))
    )
    (net (code "80") (name "Net-(U$2-*D3)") (class "Default")
      (node (ref "U$2") (pin "D3") (pinfunction "*D3_D3") (pintype "bidirectional"))
      (node (ref "U1") (pin "16") (pinfunction "B4_16") (pintype "bidirectional"))
      (node (ref "ULN1") (pin "4") (pinfunction "4_4") (pintype "bidirectional"))
    )
    (net (code "81") (name "Net-(U$2-*D5)") (class "Default")
      (node (ref "U$2") (pin "D5") (pinfunction "*D5_D5") (pintype "bidirectional"))
      (node (ref "U1") (pin "14") (pinfunction "B6_14") (pintype "bidirectional"))
      (node (ref "ULN1") (pin "6") (pinfunction "6_6") (pintype "bidirectional"))
    )
    (net (code "82") (name "Net-(U$2-*D6)") (class "Default")
      (node (ref "U$2") (pin "D6") (pinfunction "*D6_D6") (pintype "bidirectional"))
      (node (ref "U1") (pin "13") (pinfunction "B7_13") (pintype "bidirectional"))
      (node (ref "ULN1") (pin "7") (pinfunction "7_7") (pintype "bidirectional"))
    )
    (net (code "83") (name "Net-(U1-B1)") (class "Default")
      (node (ref "U$2") (pin "RX") (pinfunction "RX_RX") (pintype "bidirectional"))
      (node (ref "U1") (pin "20") (pinfunction "B1_20") (pintype "bidirectional"))
      (node (ref "ULN1") (pin "1") (pinfunction "1_1") (pintype "bidirectional"))
    )
    (net (code "84") (name "Net-(U1-B2)") (class "Default")
      (node (ref "U$2") (pin "TX") (pinfunction "TX_TX") (pintype "bidirectional"))
      (node (ref "U1") (pin "18") (pinfunction "B2_18") (pintype "bidirectional"))
      (node (ref "ULN1") (pin "2") (pinfunction "2_2") (pintype "bidirectional"))
    )
    (net (code "85") (name "Net-(U1-B3)") (class "Default")
      (node (ref "U$2") (pin "D2") (pinfunction "D2_D2") (pintype "bidirectional"))
      (node (ref "U1") (pin "17") (pinfunction "B3_17") (pintype "bidirectional"))
      (node (ref "ULN1") (pin "3") (pinfunction "3_3") (pintype "bidirectional"))
    )
    (net (code "86") (name "Net-(U1-B5)") (class "Default")
      (node (ref "U$2") (pin "D4") (pinfunction "D4_D4") (pintype "bidirectional"))
      (node (ref "U1") (pin "15") (pinfunction "B5_15") (pintype "bidirectional"))
      (node (ref "ULN1") (pin "5") (pinfunction "5_5") (pintype "bidirectional"))
    )
    (net (code "87") (name "Net-(U1-B8)") (class "Default")
      (node (ref "U$2") (pin "D7") (pinfunction "D7_D7") (pintype "bidirectional"))
      (node (ref "U1") (pin "12") (pinfunction "B8_12") (pintype "bidirectional"))
      (node (ref "ULN1") (pin "8") (pinfunction "8_8") (pintype "bidirectional"))
    )
    (net (code "88") (name "Net-(U2-B8)") (class "Default")
      (node (ref "U$2") (pin "SCL") (pinfunction "SCL_SCL") (pintype "bidirectional"))
      (node (ref "U2") (pin "12") (pinfunction "B8_12") (pintype "bidirectional"))
    )
    (net (code "89") (name "Net-(ULN2-Pad11)") (class "Default")
      (node (ref "ULN2") (pin "11") (pinfunction "11_11") (pintype "bidirectional"))
      (node (ref "USERLED") (pin "C") (pinfunction "C_C") (pintype "passive"))
    )
    (net (code "90") (name "VCC") (class "Default")
      (node (ref "C10") (pin "2") (pinfunction "2_2") (pintype "passive"))
      (node (ref "C4") (pin "+") (pinfunction "+_+") (pintype "passive"))
      (node (ref "C5") (pin "1") (pinfunction "1_1") (pintype "passive"))
      (node (ref "C6") (pin "1") (pinfunction "1_1") (pintype "passive"))
      (node (ref "C7") (pin "1") (pinfunction "1_1") (pintype "passive"))
      (node (ref "J1") (pin "16B") (pinfunction "16_16B") (pintype "passive"))
      (node (ref "J1") (pin "3B") (pinfunction "3_3B") (pintype "passive"))
      (node (ref "JP2") (pin "2") (pinfunction "2_2") (pintype "passive"))
      (node (ref "R1") (pin "C") (pinfunction "CW_C") (pintype "passive"))
      (node (ref "R3") (pin "1") (pinfunction "1_1") (pintype "passive"))
      (node (ref "R4") (pin "1") (pinfunction "1_1") (pintype "passive"))
      (node (ref "R5") (pin "1") (pinfunction "1_1") (pintype "passive"))
      (node (ref "R6") (pin "1") (pinfunction "1_1") (pintype "passive"))
      (node (ref "U$2") (pin "IOREF") (pinfunction "IOREF_IOREF") (pintype "bidirectional"))
      (node (ref "U1") (pin "19") (pinfunction "VCCB_19") (pintype "bidirectional"))
      (node (ref "U2") (pin "19") (pinfunction "VCCB_19") (pintype "bidirectional"))
      (node (ref "U3") (pin "19") (pinfunction "VCCB_19") (pintype "bidirectional"))
    )
    (net (code "91") (name "VCCIO") (class "Default")
      (node (ref "C1") (pin "1") (pinfunction "1_1") (pintype "passive"))
      (node (ref "C19") (pin "2") (pinfunction "2_2") (pintype "passive"))
      (node (ref "C2") (pin "1") (pinfunction "1_1") (pintype "passive"))
      (node (ref "C3") (pin "1") (pinfunction "1_1") (pintype "passive"))
      (node (ref "IC3") (pin "11") (pinfunction "~{RESET}_11") (pintype "bidirectional"))
      (node (ref "IC3") (pin "3") (pinfunction "VCCIO_3") (pintype "power_in"))
      (node (ref "P1") (pin "F1") (pinfunction "VDD_GPIO_F1") (pintype "passive"))
      (node (ref "P1") (pin "F2") (pinfunction "VDD_GPIO_F2") (pintype "passive"))
      (node (ref "P1") (pin "P55") (pinfunction "VDD_GPIO_P55") (pintype "passive"))
      (node (ref "P1") (pin "P56") (pinfunction "VDD_GPIO_P56") (pintype "passive"))
      (node (ref "R14") (pin "1") (pinfunction "1_1") (pintype "passive"))
      (node (ref "R15") (pin "1") (pinfunction "1_1") (pintype "passive"))
      (node (ref "U1") (pin "10") (pinfunction "OE_10") (pintype "bidirectional"))
      (node (ref "U1") (pin "2") (pinfunction "VCCA_2") (pintype "bidirectional"))
      (node (ref "U2") (pin "10") (pinfunction "OE_10") (pintype "bidirectional"))
      (node (ref "U2") (pin "2") (pinfunction "VCCA_2") (pintype "bidirectional"))
      (node (ref "U3") (pin "10") (pinfunction "OE_10") (pintype "bidirectional"))
      (node (ref "U3") (pin "2") (pinfunction "VCCA_2") (pintype "bidirectional"))
    )
    (net (code "92") (name "unconnected-(IC3-CBUS0-Pad15)") (class "Default")
      (node (ref "IC3") (pin "15") (pinfunction "CBUS0_15") (pintype "bidirectional"))
    )
    (net (code "93") (name "unconnected-(IC3-CBUS1-Pad14)") (class "Default")
      (node (ref "IC3") (pin "14") (pinfunction "CBUS1_14") (pintype "bidirectional"))
    )
    (net (code "94") (name "unconnected-(IC3-CBUS2-Pad7)") (class "Default")
      (node (ref "IC3") (pin "7") (pinfunction "CBUS2_7") (pintype "bidirectional"))
    )
    (net (code "95") (name "unconnected-(IC3-CBUS3-Pad16)") (class "Default")
      (node (ref "IC3") (pin "16") (pinfunction "CBUS3_16") (pintype "bidirectional"))
    )
    (net (code "96") (name "unconnected-(IC3-~{RTS}-Pad2)") (class "Default")
      (node (ref "IC3") (pin "2") (pinfunction "~{RTS}_2") (pintype "bidirectional"))
    )
    (net (code "97") (name "unconnected-(JTAG1-Pad2)") (class "Default")
      (node (ref "JTAG1") (pin "2") (pinfunction "2_2") (pintype "passive"))
    )
    (net (code "98") (name "unconnected-(JTAG1-Pad17)") (class "Default")
      (node (ref "JTAG1") (pin "17") (pinfunction "17_17") (pintype "passive"))
    )
    (net (code "99") (name "unconnected-(JTAG1-Pad19)") (class "Default")
      (node (ref "JTAG1") (pin "19") (pinfunction "19_19") (pintype "passive"))
    )
    (net (code "100") (name "unconnected-(JTAGD-S-Pad12)") (class "Default")
      (node (ref "JTAG") (pin "12") (pinfunction "S_12") (pintype "passive"))
    )
    (net (code "101") (name "unconnected-(JTAGF-S-Pad14)") (class "Default")
      (node (ref "JTAG") (pin "14") (pinfunction "S_14") (pintype "passive"))
    )
    (net (code "102") (name "unconnected-(P1A-GPIO11_N-PadF28)") (class "Default")
      (node (ref "P1") (pin "F28") (pinfunction "GPIO11_N_F28") (pintype "bidirectional"))
    )
    (net (code "103") (name "unconnected-(P1A-GPIO12_N-PadF33)") (class "Default")
      (node (ref "P1") (pin "F33") (pinfunction "GPIO12_N_F33") (pintype "bidirectional"))
    )
    (net (code "104") (name "unconnected-(P1A-GPIO12_P-PadF35)") (class "Default")
      (node (ref "P1") (pin "F35") (pinfunction "GPIO12_P_F35") (pintype "bidirectional"))
    )
    (net (code "105") (name "unconnected-(P1A-GPIO13_N-PadF34)") (class "Default")
      (node (ref "P1") (pin "F34") (pinfunction "GPIO13_N_F34") (pintype "bidirectional"))
    )
    (net (code "106") (name "unconnected-(P1A-GPIO13_P-PadF36)") (class "Default")
      (node (ref "P1") (pin "F36") (pinfunction "GPIO13_P_F36") (pintype "bidirectional"))
    )
    (net (code "107") (name "unconnected-(P1A-GPIO14_N-PadF37)") (class "Default")
      (node (ref "P1") (pin "F37") (pinfunction "GPIO14_N_F37") (pintype "bidirectional"))
    )
    (net (code "108") (name "unconnected-(P1A-GPIO14_P-PadF39)") (class "Default")
      (node (ref "P1") (pin "F39") (pinfunction "GPIO14_P_F39") (pintype "bidirectional"))
    )
    (net (code "109") (name "unconnected-(P1A-GPIO15_N-PadF38)") (class "Default")
      (node (ref "P1") (pin "F38") (pinfunction "GPIO15_N_F38") (pintype "bidirectional"))
    )
    (net (code "110") (name "unconnected-(P1A-GPIO15_P-PadF40)") (class "Default")
      (node (ref "P1") (pin "F40") (pinfunction "GPIO15_P_F40") (pintype "bidirectional"))
    )
    (net (code "111") (name "unconnected-(P1A-GPIO16_N-PadF43)") (class "Default")
      (node (ref "P1") (pin "F43") (pinfunction "GPIO16_N_F43") (pintype "bidirectional"))
    )
    (net (code "112") (name "unconnected-(P1A-GPIO16_P-PadF45)") (class "Default")
      (node (ref "P1") (pin "F45") (pinfunction "GPIO16_P_F45") (pintype "bidirectional"))
    )
    (net (code "113") (name "unconnected-(P1A-GPIO17_N-PadF44)") (class "Default")
      (node (ref "P1") (pin "F44") (pinfunction "GPIO17_N_F44") (pintype "bidirectional"))
    )
    (net (code "114") (name "unconnected-(P1A-GPIO17_P-PadF46)") (class "Default")
      (node (ref "P1") (pin "F46") (pinfunction "GPIO17_P_F46") (pintype "bidirectional"))
    )
    (net (code "115") (name "unconnected-(P1A-GPIO18_N-PadF47)") (class "Default")
      (node (ref "P1") (pin "F47") (pinfunction "GPIO18_N_F47") (pintype "bidirectional"))
    )
    (net (code "116") (name "unconnected-(P1A-GPIO18_P-PadF49)") (class "Default")
      (node (ref "P1") (pin "F49") (pinfunction "GPIO18_P_F49") (pintype "bidirectional"))
    )
    (net (code "117") (name "unconnected-(P1A-GPIO19_N-PadF48)") (class "Default")
      (node (ref "P1") (pin "F48") (pinfunction "GPIO19_N_F48") (pintype "bidirectional"))
    )
    (net (code "118") (name "unconnected-(P1A-GPIO19_P-PadF50)") (class "Default")
      (node (ref "P1") (pin "F50") (pinfunction "GPIO19_P_F50") (pintype "bidirectional"))
    )
    (net (code "119") (name "unconnected-(P1A-GPIO20_N-PadF53)") (class "Default")
      (node (ref "P1") (pin "F53") (pinfunction "GPIO20_N_F53") (pintype "bidirectional"))
    )
    (net (code "120") (name "unconnected-(P1A-GPIO20_P-PadF55)") (class "Default")
      (node (ref "P1") (pin "F55") (pinfunction "GPIO20_P_F55") (pintype "bidirectional"))
    )
    (net (code "121") (name "unconnected-(P1A-GPIO21_N-PadF54)") (class "Default")
      (node (ref "P1") (pin "F54") (pinfunction "GPIO21_N_F54") (pintype "bidirectional"))
    )
    (net (code "122") (name "unconnected-(P1A-GPIO21_P-PadF56)") (class "Default")
      (node (ref "P1") (pin "F56") (pinfunction "GPIO21_P_F56") (pintype "bidirectional"))
    )
    (net (code "123") (name "unconnected-(P1A-GPIO22_N-PadF57)") (class "Default")
      (node (ref "P1") (pin "F57") (pinfunction "GPIO22_N_F57") (pintype "bidirectional"))
    )
    (net (code "124") (name "unconnected-(P1A-GPIO22_P-PadF59)") (class "Default")
      (node (ref "P1") (pin "F59") (pinfunction "GPIO22_P_F59") (pintype "bidirectional"))
    )
    (net (code "125") (name "unconnected-(P1A-GPIO23_N-PadF58)") (class "Default")
      (node (ref "P1") (pin "F58") (pinfunction "GPIO23_N_F58") (pintype "bidirectional"))
    )
    (net (code "126") (name "unconnected-(P1A-GPIO23_P-PadF60)") (class "Default")
      (node (ref "P1") (pin "F60") (pinfunction "GPIO23_P_F60") (pintype "bidirectional"))
    )
    (net (code "127") (name "unconnected-(P1B-1P0V-PadP43)") (class "Default")
      (node (ref "P1") (pin "P43") (pinfunction "1P0V_P43") (pintype "passive"))
    )
    (net (code "128") (name "unconnected-(P1B-1P0V-PadP44)") (class "Default")
      (node (ref "P1") (pin "P44") (pinfunction "1P0V_P44") (pintype "passive"))
    )
    (net (code "129") (name "unconnected-(P1B-1P8V-PadP49)") (class "Default")
      (node (ref "P1") (pin "P49") (pinfunction "1P8V_P49") (pintype "passive"))
    )
    (net (code "130") (name "unconnected-(P1B-1P8V-PadP50)") (class "Default")
      (node (ref "P1") (pin "P50") (pinfunction "1P8V_P50") (pintype "passive"))
    )
    (net (code "131") (name "unconnected-(P1B-1P35V-PadP47)") (class "Default")
      (node (ref "P1") (pin "P47") (pinfunction "1P35V_P47") (pintype "passive"))
    )
    (net (code "132") (name "unconnected-(P1B-1P35V-PadP48)") (class "Default")
      (node (ref "P1") (pin "P48") (pinfunction "1P35V_P48") (pintype "passive"))
    )
    (net (code "133") (name "unconnected-(P1B-2P5V-PadP57)") (class "Default")
      (node (ref "P1") (pin "P57") (pinfunction "2P5V_P57") (pintype "passive"))
    )
    (net (code "134") (name "unconnected-(P1B-2P5V-PadP58)") (class "Default")
      (node (ref "P1") (pin "P58") (pinfunction "2P5V_P58") (pintype "passive"))
    )
    (net (code "135") (name "unconnected-(P1B-3P3V-PadP59)") (class "Default")
      (node (ref "P1") (pin "P59") (pinfunction "3P3V_P59") (pintype "passive"))
    )
    (net (code "136") (name "unconnected-(P1B-DSP_FLAG-PadP23)") (class "Default")
      (node (ref "P1") (pin "P23") (pinfunction "DSP_FLAG_P23") (pintype "output"))
    )
    (net (code "137") (name "unconnected-(P1B-DSP_XID0-PadP13)") (class "Default")
      (node (ref "P1") (pin "P13") (pinfunction "DSP_XID0_P13") (pintype "input"))
    )
    (net (code "138") (name "unconnected-(P1B-DSP_XID1-PadP15)") (class "Default")
      (node (ref "P1") (pin "P15") (pinfunction "DSP_XID1_P15") (pintype "input"))
    )
    (net (code "139") (name "unconnected-(P1B-DSP_XID2-PadP17)") (class "Default")
      (node (ref "P1") (pin "P17") (pinfunction "DSP_XID2_P17") (pintype "input"))
    )
    (net (code "140") (name "unconnected-(P1B-DSP_XID3-PadP19)") (class "Default")
      (node (ref "P1") (pin "P19") (pinfunction "DSP_XID3_P19") (pintype "input"))
    )
    (net (code "141") (name "unconnected-(P1B-DSP_YID0-PadP14)") (class "Default")
      (node (ref "P1") (pin "P14") (pinfunction "DSP_YID0_P14") (pintype "input"))
    )
    (net (code "142") (name "unconnected-(P1B-DSP_YID1-PadP16)") (class "Default")
      (node (ref "P1") (pin "P16") (pinfunction "DSP_YID1_P16") (pintype "input"))
    )
    (net (code "143") (name "unconnected-(P1B-DSP_YID2-PadP18)") (class "Default")
      (node (ref "P1") (pin "P18") (pinfunction "DSP_YID2_P18") (pintype "input"))
    )
    (net (code "144") (name "unconnected-(P1B-DSP_YID3-PadP20)") (class "Default")
      (node (ref "P1") (pin "P20") (pinfunction "DSP_YID3_P20") (pintype "input"))
    )
    (net (code "145") (name "unconnected-(P1B-I2C_SCL-PadP3)") (class "Default")
      (node (ref "P1") (pin "P3") (pinfunction "I2C_SCL_P3") (pintype "bidirectional"))
    )
    (net (code "146") (name "unconnected-(P1B-I2C_SDA-PadP4)") (class "Default")
      (node (ref "P1") (pin "P4") (pinfunction "I2C_SDA_P4") (pintype "bidirectional"))
    )
    (net (code "147") (name "unconnected-(P1B-NC-PadP10)") (class "Default")
      (node (ref "P1") (pin "P10") (pinfunction "NC_P10") (pintype "no_connect"))
    )
    (net (code "148") (name "unconnected-(P1B-PROG_IO-PadP9)") (class "Default")
      (node (ref "P1") (pin "P9") (pinfunction "PROG_IO_P9") (pintype "bidirectional"))
    )
    (net (code "149") (name "unconnected-(P1B-REG_EN1-PadP5)") (class "Default")
      (node (ref "P1") (pin "P5") (pinfunction "REG_EN1_P5") (pintype "input"))
    )
    (net (code "150") (name "unconnected-(P1B-REG_EN2-PadP6)") (class "Default")
      (node (ref "P1") (pin "P6") (pinfunction "REG_EN2_P6") (pintype "input"))
    )
    (net (code "151") (name "unconnected-(P1B-REG_EN3-PadP7)") (class "Default")
      (node (ref "P1") (pin "P7") (pinfunction "REG_EN3_P7") (pintype "input"))
    )
    (net (code "152") (name "unconnected-(P1B-REG_EN4-PadP8)") (class "Default")
      (node (ref "P1") (pin "P8") (pinfunction "REG_EN4_P8") (pintype "input"))
    )
    (net (code "153") (name "unconnected-(P1B-SPDIF-PadP27)") (class "Default")
      (node (ref "P1") (pin "P27") (pinfunction "SPDIF_P27") (pintype "output"))
    )
    (net (code "154") (name "unconnected-(P1B-TURBO_MODE-PadP25)") (class "Default")
      (node (ref "P1") (pin "P25") (pinfunction "TURBO_MODE_P25") (pintype "output"))
    )
    (net (code "155") (name "unconnected-(P1B-VADC_N-PadP33)") (class "Default")
      (node (ref "P1") (pin "P33") (pinfunction "VADC_N_P33") (pintype "input"))
    )
    (net (code "156") (name "unconnected-(P1B-VADC_P-PadP34)") (class "Default")
      (node (ref "P1") (pin "P34") (pinfunction "VADC_P_P34") (pintype "input"))
    )
    (net (code "157") (name "unconnected-(P1B-VDD_ADJ-PadP53)") (class "Default")
      (node (ref "P1") (pin "P53") (pinfunction "VDD_ADJ_P53") (pintype "passive"))
    )
    (net (code "158") (name "unconnected-(P1B-VDD_ADJ-PadP54)") (class "Default")
      (node (ref "P1") (pin "P54") (pinfunction "VDD_ADJ_P54") (pintype "passive"))
    )
    (net (code "159") (name "unconnected-(P1B-VDD_DSP-PadP45)") (class "Default")
      (node (ref "P1") (pin "P45") (pinfunction "VDD_DSP_P45") (pintype "passive"))
    )
    (net (code "160") (name "unconnected-(P1B-VDD_DSP-PadP46)") (class "Default")
      (node (ref "P1") (pin "P46") (pinfunction "VDD_DSP_P46") (pintype "passive"))
    )
    (net (code "161") (name "unconnected-(RESET-S-PadB)") (class "Default")
      (node (ref "RESET") (pin "B") (pinfunction "S_B") (pintype "passive"))
    )
    (net (code "162") (name "unconnected-(SERIALB-USBID-PadID)") (class "Default")
      (node (ref "SERIAL") (pin "ID") (pinfunction "USBID_ID") (pintype "bidirectional"))
    )
    (net (code "163") (name "unconnected-(SW0-P-PadA)") (class "Default")
      (node (ref "SW0") (pin "A") (pinfunction "P_A") (pintype "passive"))
    )
    (net (code "164") (name "unconnected-(SW1-P-PadA)") (class "Default")
      (node (ref "SW1") (pin "A") (pinfunction "P_A") (pintype "passive"))
    )
    (net (code "165") (name "unconnected-(SW2-P-PadA)") (class "Default")
      (node (ref "SW2") (pin "A") (pinfunction "P_A") (pintype "passive"))
    )
    (net (code "166") (name "unconnected-(SW3-P-PadA)") (class "Default")
      (node (ref "SW3") (pin "A") (pinfunction "P_A") (pintype "passive"))
    )
    (net (code "167") (name "unconnected-(U$2-PadAREF)") (class "Default")
      (node (ref "U$2") (pin "AREF") (pinfunction "AREF_AREF") (pintype "bidirectional"))
    )
    (net (code "168") (name "unconnected-(U$2-PadRES)") (class "Default")
      (node (ref "U$2") (pin "RES") (pinfunction "RES_RES") (pintype "bidirectional"))
    )
    (net (code "169") (name "unconnected-(U2-A6-Pad7)") (class "Default")
      (node (ref "U2") (pin "7") (pinfunction "A6_7") (pintype "bidirectional"))
    )
    (net (code "170") (name "unconnected-(ULN2-Pad12)") (class "Default")
      (node (ref "ULN2") (pin "12") (pinfunction "12_12") (pintype "bidirectional"))
    )
    (net (code "171") (name "unconnected-(ULN2-Pad13)") (class "Default")
      (node (ref "ULN2") (pin "13") (pinfunction "13_13") (pintype "bidirectional"))
    )
    (net (code "172") (name "unconnected-(ULN2-Pad14)") (class "Default")
      (node (ref "ULN2") (pin "14") (pinfunction "14_14") (pintype "bidirectional"))
    )
    (net (code "173") (name "unconnected-(ULN2-Pad15)") (class "Default")
      (node (ref "ULN2") (pin "15") (pinfunction "15_15") (pintype "bidirectional"))
    )
    (net (code "174") (name "unconnected-(ULN2-Pad16)") (class "Default")
      (node (ref "ULN2") (pin "16") (pinfunction "16_16") (pintype "bidirectional"))
    )
    (net (code "175") (name "unconnected-(ULN2-Pad17)") (class "Default")
      (node (ref "ULN2") (pin "17") (pinfunction "17_17") (pintype "bidirectional"))
    )
    (net (code "176") (name "unconnected-(ULN2-Pad18)") (class "Default")
      (node (ref "ULN2") (pin "18") (pinfunction "18_18") (pintype "bidirectional"))
    )
  )
)
